# A7_POWER.net
KiCad netlist of a schematic drawn in Altium Designer
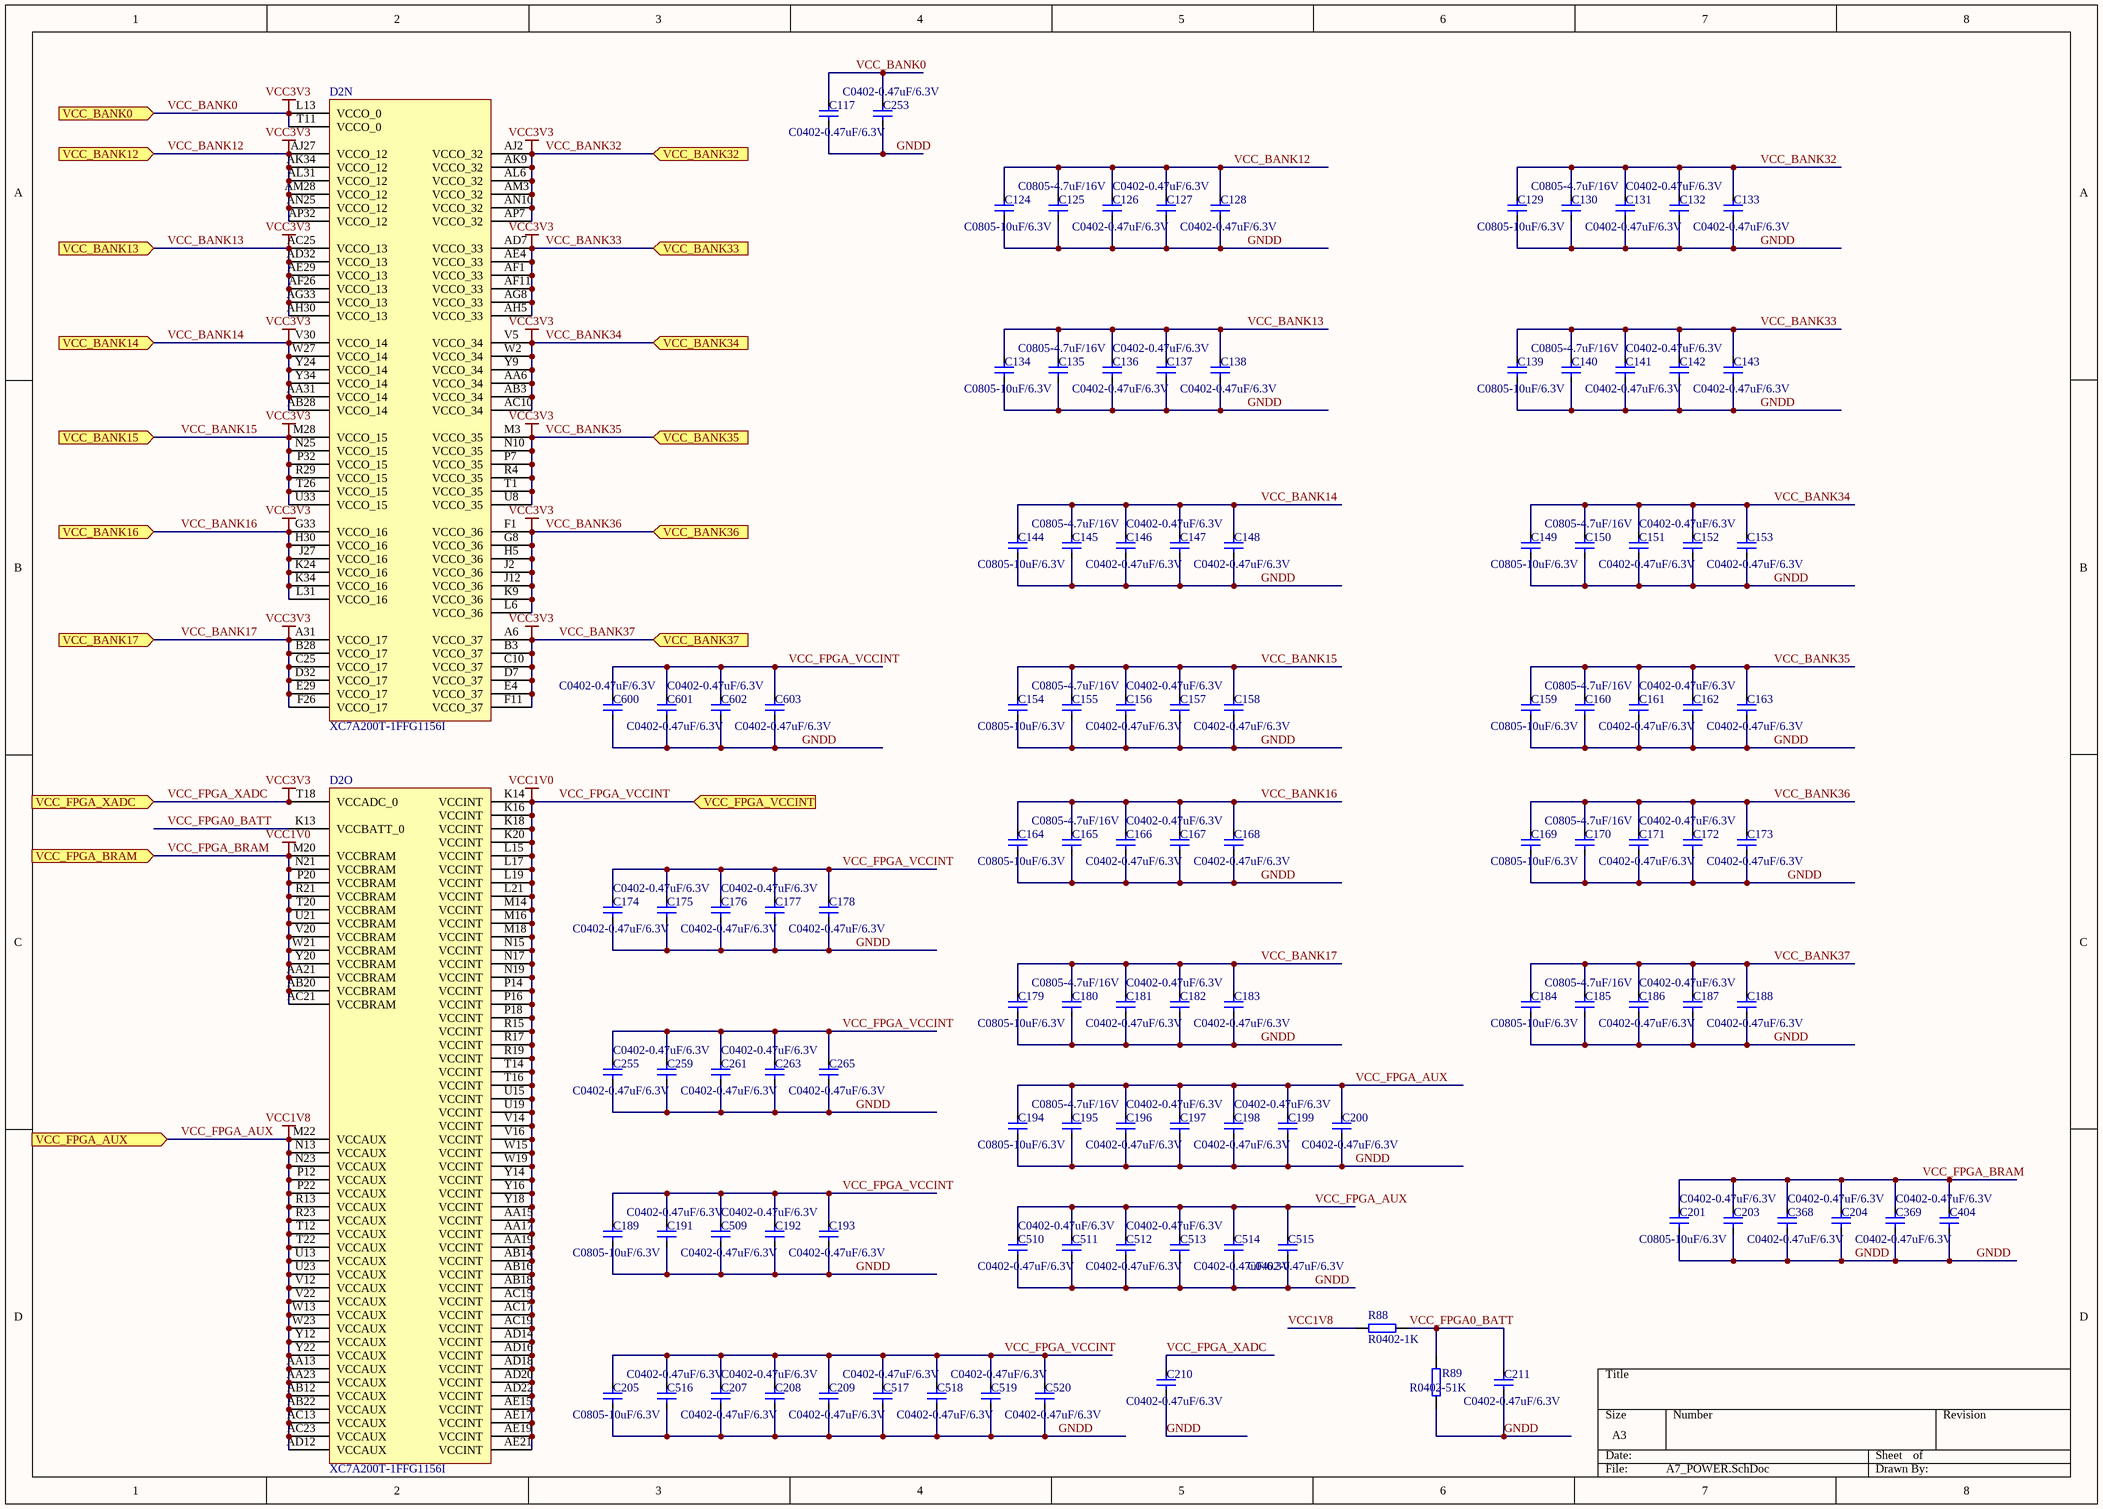
[diagram p0: A7_POWER.SchDoc]

(export (version "E")
  (design (tool "Eeschema 10.0.6"))
  (components
    (comp (ref "C117")
      (value "C0402-0.47uF/6.3V")
      (footprint "C0402")
      (description "X7R")
      (fields (field (name "SCHEMATIC_PART") "CAP") (field (name "MANUFACTURER") "SAMSUNG"))
      (libsource (lib "Database_Libs1") (part "CAP"))
    )
    (comp (ref "C124")
      (value "C0805-10uF/6.3V")
      (footprint "C0805")
      (fields (field (name "SCHEMATIC_PART") "CAP"))
      (libsource (lib "Database_Libs1") (part "CAP"))
    )
    (comp (ref "C125")
      (value "C0805-4.7uF/16V")
      (footprint "C0805")
      (description "X7R")
      (fields (field (name "SCHEMATIC_PART") "CAP") (field (name "MANUFACTURER") "SAMSUNG"))
      (libsource (lib "Database_Libs1") (part "CAP"))
    )
    (comp (ref "C126")
      (value "C0402-0.47uF/6.3V")
      (footprint "C0402")
      (description "X7R")
      (fields (field (name "SCHEMATIC_PART") "CAP") (field (name "MANUFACTURER") "SAMSUNG"))
      (libsource (lib "Database_Libs1") (part "CAP"))
    )
    (comp (ref "C127")
      (value "C0402-0.47uF/6.3V")
      (footprint "C0402")
      (description "X7R")
      (fields (field (name "SCHEMATIC_PART") "CAP") (field (name "MANUFACTURER") "SAMSUNG"))
      (libsource (lib "Database_Libs1") (part "CAP"))
    )
    (comp (ref "C128")
      (value "C0402-0.47uF/6.3V")
      (footprint "C0402")
      (description "X7R")
      (fields (field (name "SCHEMATIC_PART") "CAP") (field (name "MANUFACTURER") "SAMSUNG"))
      (libsource (lib "Database_Libs1") (part "CAP"))
    )
    (comp (ref "C129")
      (value "C0805-10uF/6.3V")
      (footprint "C0805")
      (fields (field (name "SCHEMATIC_PART") "CAP"))
      (libsource (lib "Database_Libs1") (part "CAP"))
    )
    (comp (ref "C130")
      (value "C0805-4.7uF/16V")
      (footprint "C0805")
      (description "X7R")
      (fields (field (name "SCHEMATIC_PART") "CAP") (field (name "MANUFACTURER") "SAMSUNG"))
      (libsource (lib "Database_Libs1") (part "CAP"))
    )
    (comp (ref "C131")
      (value "C0402-0.47uF/6.3V")
      (footprint "C0402")
      (description "X7R")
      (fields (field (name "SCHEMATIC_PART") "CAP") (field (name "MANUFACTURER") "SAMSUNG"))
      (libsource (lib "Database_Libs1") (part "CAP"))
    )
    (comp (ref "C132")
      (value "C0402-0.47uF/6.3V")
      (footprint "C0402")
      (description "X7R")
      (fields (field (name "SCHEMATIC_PART") "CAP") (field (name "MANUFACTURER") "SAMSUNG"))
      (libsource (lib "Database_Libs1") (part "CAP"))
    )
    (comp (ref "C133")
      (value "C0402-0.47uF/6.3V")
      (footprint "C0402")
      (description "X7R")
      (fields (field (name "SCHEMATIC_PART") "CAP") (field (name "MANUFACTURER") "SAMSUNG"))
      (libsource (lib "Database_Libs1") (part "CAP"))
    )
    (comp (ref "C134")
      (value "C0805-10uF/6.3V")
      (footprint "C0805")
      (fields (field (name "SCHEMATIC_PART") "CAP"))
      (libsource (lib "Database_Libs1") (part "CAP"))
    )
    (comp (ref "C135")
      (value "C0805-4.7uF/16V")
      (footprint "C0805")
      (description "X7R")
      (fields (field (name "SCHEMATIC_PART") "CAP") (field (name "MANUFACTURER") "SAMSUNG"))
      (libsource (lib "Database_Libs1") (part "CAP"))
    )
    (comp (ref "C136")
      (value "C0402-0.47uF/6.3V")
      (footprint "C0402")
      (description "X7R")
      (fields (field (name "SCHEMATIC_PART") "CAP") (field (name "MANUFACTURER") "SAMSUNG"))
      (libsource (lib "Database_Libs1") (part "CAP"))
    )
    (comp (ref "C137")
      (value "C0402-0.47uF/6.3V")
      (footprint "C0402")
      (description "X7R")
      (fields (field (name "SCHEMATIC_PART") "CAP") (field (name "MANUFACTURER") "SAMSUNG"))
      (libsource (lib "Database_Libs1") (part "CAP"))
    )
    (comp (ref "C138")
      (value "C0402-0.47uF/6.3V")
      (footprint "C0402")
      (description "X7R")
      (fields (field (name "SCHEMATIC_PART") "CAP") (field (name "MANUFACTURER") "SAMSUNG"))
      (libsource (lib "Database_Libs1") (part "CAP"))
    )
    (comp (ref "C139")
      (value "C0805-10uF/6.3V")
      (footprint "C0805")
      (fields (field (name "SCHEMATIC_PART") "CAP"))
      (libsource (lib "Database_Libs1") (part "CAP"))
    )
    (comp (ref "C140")
      (value "C0805-4.7uF/16V")
      (footprint "C0805")
      (description "X7R")
      (fields (field (name "SCHEMATIC_PART") "CAP") (field (name "MANUFACTURER") "SAMSUNG"))
      (libsource (lib "Database_Libs1") (part "CAP"))
    )
    (comp (ref "C141")
      (value "C0402-0.47uF/6.3V")
      (footprint "C0402")
      (description "X7R")
      (fields (field (name "SCHEMATIC_PART") "CAP") (field (name "MANUFACTURER") "SAMSUNG"))
      (libsource (lib "Database_Libs1") (part "CAP"))
    )
    (comp (ref "C142")
      (value "C0402-0.47uF/6.3V")
      (footprint "C0402")
      (description "X7R")
      (fields (field (name "SCHEMATIC_PART") "CAP") (field (name "MANUFACTURER") "SAMSUNG"))
      (libsource (lib "Database_Libs1") (part "CAP"))
    )
    (comp (ref "C143")
      (value "C0402-0.47uF/6.3V")
      (footprint "C0402")
      (description "X7R")
      (fields (field (name "SCHEMATIC_PART") "CAP") (field (name "MANUFACTURER") "SAMSUNG"))
      (libsource (lib "Database_Libs1") (part "CAP"))
    )
    (comp (ref "C144")
      (value "C0805-10uF/6.3V")
      (footprint "C0805")
      (fields (field (name "SCHEMATIC_PART") "CAP"))
      (libsource (lib "Database_Libs1") (part "CAP"))
    )
    (comp (ref "C145")
      (value "C0805-4.7uF/16V")
      (footprint "C0805")
      (description "X7R")
      (fields (field (name "SCHEMATIC_PART") "CAP") (field (name "MANUFACTURER") "SAMSUNG"))
      (libsource (lib "Database_Libs1") (part "CAP"))
    )
    (comp (ref "C146")
      (value "C0402-0.47uF/6.3V")
      (footprint "C0402")
      (description "X7R")
      (fields (field (name "SCHEMATIC_PART") "CAP") (field (name "MANUFACTURER") "SAMSUNG"))
      (libsource (lib "Database_Libs1") (part "CAP"))
    )
    (comp (ref "C147")
      (value "C0402-0.47uF/6.3V")
      (footprint "C0402")
      (description "X7R")
      (fields (field (name "SCHEMATIC_PART") "CAP") (field (name "MANUFACTURER") "SAMSUNG"))
      (libsource (lib "Database_Libs1") (part "CAP"))
    )
    (comp (ref "C148")
      (value "C0402-0.47uF/6.3V")
      (footprint "C0402")
      (description "X7R")
      (fields (field (name "SCHEMATIC_PART") "CAP") (field (name "MANUFACTURER") "SAMSUNG"))
      (libsource (lib "Database_Libs1") (part "CAP"))
    )
    (comp (ref "C149")
      (value "C0805-10uF/6.3V")
      (footprint "C0805")
      (fields (field (name "SCHEMATIC_PART") "CAP"))
      (libsource (lib "Database_Libs1") (part "CAP"))
    )
    (comp (ref "C150")
      (value "C0805-4.7uF/16V")
      (footprint "C0805")
      (description "X7R")
      (fields (field (name "SCHEMATIC_PART") "CAP") (field (name "MANUFACTURER") "SAMSUNG"))
      (libsource (lib "Database_Libs1") (part "CAP"))
    )
    (comp (ref "C151")
      (value "C0402-0.47uF/6.3V")
      (footprint "C0402")
      (description "X7R")
      (fields (field (name "SCHEMATIC_PART") "CAP") (field (name "MANUFACTURER") "SAMSUNG"))
      (libsource (lib "Database_Libs1") (part "CAP"))
    )
    (comp (ref "C152")
      (value "C0402-0.47uF/6.3V")
      (footprint "C0402")
      (description "X7R")
      (fields (field (name "SCHEMATIC_PART") "CAP") (field (name "MANUFACTURER") "SAMSUNG"))
      (libsource (lib "Database_Libs1") (part "CAP"))
    )
    (comp (ref "C153")
      (value "C0402-0.47uF/6.3V")
      (footprint "C0402")
      (description "X7R")
      (fields (field (name "SCHEMATIC_PART") "CAP") (field (name "MANUFACTURER") "SAMSUNG"))
      (libsource (lib "Database_Libs1") (part "CAP"))
    )
    (comp (ref "C154")
      (value "C0805-10uF/6.3V")
      (footprint "C0805")
      (fields (field (name "SCHEMATIC_PART") "CAP"))
      (libsource (lib "Database_Libs1") (part "CAP"))
    )
    (comp (ref "C155")
      (value "C0805-4.7uF/16V")
      (footprint "C0805")
      (description "X7R")
      (fields (field (name "SCHEMATIC_PART") "CAP") (field (name "MANUFACTURER") "SAMSUNG"))
      (libsource (lib "Database_Libs1") (part "CAP"))
    )
    (comp (ref "C156")
      (value "C0402-0.47uF/6.3V")
      (footprint "C0402")
      (description "X7R")
      (fields (field (name "SCHEMATIC_PART") "CAP") (field (name "MANUFACTURER") "SAMSUNG"))
      (libsource (lib "Database_Libs1") (part "CAP"))
    )
    (comp (ref "C157")
      (value "C0402-0.47uF/6.3V")
      (footprint "C0402")
      (description "X7R")
      (fields (field (name "SCHEMATIC_PART") "CAP") (field (name "MANUFACTURER") "SAMSUNG"))
      (libsource (lib "Database_Libs1") (part "CAP"))
    )
    (comp (ref "C158")
      (value "C0402-0.47uF/6.3V")
      (footprint "C0402")
      (description "X7R")
      (fields (field (name "SCHEMATIC_PART") "CAP") (field (name "MANUFACTURER") "SAMSUNG"))
      (libsource (lib "Database_Libs1") (part "CAP"))
    )
    (comp (ref "C159")
      (value "C0805-10uF/6.3V")
      (footprint "C0805")
      (fields (field (name "SCHEMATIC_PART") "CAP"))
      (libsource (lib "Database_Libs1") (part "CAP"))
    )
    (comp (ref "C160")
      (value "C0805-4.7uF/16V")
      (footprint "C0805")
      (description "X7R")
      (fields (field (name "SCHEMATIC_PART") "CAP") (field (name "MANUFACTURER") "SAMSUNG"))
      (libsource (lib "Database_Libs1") (part "CAP"))
    )
    (comp (ref "C161")
      (value "C0402-0.47uF/6.3V")
      (footprint "C0402")
      (description "X7R")
      (fields (field (name "SCHEMATIC_PART") "CAP") (field (name "MANUFACTURER") "SAMSUNG"))
      (libsource (lib "Database_Libs1") (part "CAP"))
    )
    (comp (ref "C162")
      (value "C0402-0.47uF/6.3V")
      (footprint "C0402")
      (description "X7R")
      (fields (field (name "SCHEMATIC_PART") "CAP") (field (name "MANUFACTURER") "SAMSUNG"))
      (libsource (lib "Database_Libs1") (part "CAP"))
    )
    (comp (ref "C163")
      (value "C0402-0.47uF/6.3V")
      (footprint "C0402")
      (description "X7R")
      (fields (field (name "SCHEMATIC_PART") "CAP") (field (name "MANUFACTURER") "SAMSUNG"))
      (libsource (lib "Database_Libs1") (part "CAP"))
    )
    (comp (ref "C164")
      (value "C0805-10uF/6.3V")
      (footprint "C0805")
      (fields (field (name "SCHEMATIC_PART") "CAP"))
      (libsource (lib "Database_Libs1") (part "CAP"))
    )
    (comp (ref "C165")
      (value "C0805-4.7uF/16V")
      (footprint "C0805")
      (description "X7R")
      (fields (field (name "SCHEMATIC_PART") "CAP") (field (name "MANUFACTURER") "SAMSUNG"))
      (libsource (lib "Database_Libs1") (part "CAP"))
    )
    (comp (ref "C166")
      (value "C0402-0.47uF/6.3V")
      (footprint "C0402")
      (description "X7R")
      (fields (field (name "SCHEMATIC_PART") "CAP") (field (name "MANUFACTURER") "SAMSUNG"))
      (libsource (lib "Database_Libs1") (part "CAP"))
    )
    (comp (ref "C167")
      (value "C0402-0.47uF/6.3V")
      (footprint "C0402")
      (description "X7R")
      (fields (field (name "SCHEMATIC_PART") "CAP") (field (name "MANUFACTURER") "SAMSUNG"))
      (libsource (lib "Database_Libs1") (part "CAP"))
    )
    (comp (ref "C168")
      (value "C0402-0.47uF/6.3V")
      (footprint "C0402")
      (description "X7R")
      (fields (field (name "SCHEMATIC_PART") "CAP") (field (name "MANUFACTURER") "SAMSUNG"))
      (libsource (lib "Database_Libs1") (part "CAP"))
    )
    (comp (ref "C169")
      (value "C0805-10uF/6.3V")
      (footprint "C0805")
      (fields (field (name "SCHEMATIC_PART") "CAP"))
      (libsource (lib "Database_Libs1") (part "CAP"))
    )
    (comp (ref "C170")
      (value "C0805-4.7uF/16V")
      (footprint "C0805")
      (description "X7R")
      (fields (field (name "SCHEMATIC_PART") "CAP") (field (name "MANUFACTURER") "SAMSUNG"))
      (libsource (lib "Database_Libs1") (part "CAP"))
    )
    (comp (ref "C171")
      (value "C0402-0.47uF/6.3V")
      (footprint "C0402")
      (description "X7R")
      (fields (field (name "SCHEMATIC_PART") "CAP") (field (name "MANUFACTURER") "SAMSUNG"))
      (libsource (lib "Database_Libs1") (part "CAP"))
    )
    (comp (ref "C172")
      (value "C0402-0.47uF/6.3V")
      (footprint "C0402")
      (description "X7R")
      (fields (field (name "SCHEMATIC_PART") "CAP") (field (name "MANUFACTURER") "SAMSUNG"))
      (libsource (lib "Database_Libs1") (part "CAP"))
    )
    (comp (ref "C173")
      (value "C0402-0.47uF/6.3V")
      (footprint "C0402")
      (description "X7R")
      (fields (field (name "SCHEMATIC_PART") "CAP") (field (name "MANUFACTURER") "SAMSUNG"))
      (libsource (lib "Database_Libs1") (part "CAP"))
    )
    (comp (ref "C174")
      (value "C0402-0.47uF/6.3V")
      (footprint "C0402")
      (description "X7R")
      (fields (field (name "SCHEMATIC_PART") "CAP") (field (name "MANUFACTURER") "SAMSUNG"))
      (libsource (lib "Database_Libs1") (part "CAP"))
    )
    (comp (ref "C175")
      (value "C0402-0.47uF/6.3V")
      (footprint "C0402")
      (description "X7R")
      (fields (field (name "SCHEMATIC_PART") "CAP") (field (name "MANUFACTURER") "SAMSUNG"))
      (libsource (lib "Database_Libs1") (part "CAP"))
    )
    (comp (ref "C176")
      (value "C0402-0.47uF/6.3V")
      (footprint "C0402")
      (description "X7R")
      (fields (field (name "SCHEMATIC_PART") "CAP") (field (name "MANUFACTURER") "SAMSUNG"))
      (libsource (lib "Database_Libs1") (part "CAP"))
    )
    (comp (ref "C177")
      (value "C0402-0.47uF/6.3V")
      (footprint "C0402")
      (description "X7R")
      (fields (field (name "SCHEMATIC_PART") "CAP") (field (name "MANUFACTURER") "SAMSUNG"))
      (libsource (lib "Database_Libs1") (part "CAP"))
    )
    (comp (ref "C178")
      (value "C0402-0.47uF/6.3V")
      (footprint "C0402")
      (description "X7R")
      (fields (field (name "SCHEMATIC_PART") "CAP") (field (name "MANUFACTURER") "SAMSUNG"))
      (libsource (lib "Database_Libs1") (part "CAP"))
    )
    (comp (ref "C179")
      (value "C0805-10uF/6.3V")
      (footprint "C0805")
      (fields (field (name "SCHEMATIC_PART") "CAP"))
      (libsource (lib "Database_Libs1") (part "CAP"))
    )
    (comp (ref "C180")
      (value "C0805-4.7uF/16V")
      (footprint "C0805")
      (description "X7R")
      (fields (field (name "SCHEMATIC_PART") "CAP") (field (name "MANUFACTURER") "SAMSUNG"))
      (libsource (lib "Database_Libs1") (part "CAP"))
    )
    (comp (ref "C181")
      (value "C0402-0.47uF/6.3V")
      (footprint "C0402")
      (description "X7R")
      (fields (field (name "SCHEMATIC_PART") "CAP") (field (name "MANUFACTURER") "SAMSUNG"))
      (libsource (lib "Database_Libs1") (part "CAP"))
    )
    (comp (ref "C182")
      (value "C0402-0.47uF/6.3V")
      (footprint "C0402")
      (description "X7R")
      (fields (field (name "SCHEMATIC_PART") "CAP") (field (name "MANUFACTURER") "SAMSUNG"))
      (libsource (lib "Database_Libs1") (part "CAP"))
    )
    (comp (ref "C183")
      (value "C0402-0.47uF/6.3V")
      (footprint "C0402")
      (description "X7R")
      (fields (field (name "SCHEMATIC_PART") "CAP") (field (name "MANUFACTURER") "SAMSUNG"))
      (libsource (lib "Database_Libs1") (part "CAP"))
    )
    (comp (ref "C184")
      (value "C0805-10uF/6.3V")
      (footprint "C0805")
      (fields (field (name "SCHEMATIC_PART") "CAP"))
      (libsource (lib "Database_Libs1") (part "CAP"))
    )
    (comp (ref "C185")
      (value "C0805-4.7uF/16V")
      (footprint "C0805")
      (description "X7R")
      (fields (field (name "SCHEMATIC_PART") "CAP") (field (name "MANUFACTURER") "SAMSUNG"))
      (libsource (lib "Database_Libs1") (part "CAP"))
    )
    (comp (ref "C186")
      (value "C0402-0.47uF/6.3V")
      (footprint "C0402")
      (description "X7R")
      (fields (field (name "SCHEMATIC_PART") "CAP") (field (name "MANUFACTURER") "SAMSUNG"))
      (libsource (lib "Database_Libs1") (part "CAP"))
    )
    (comp (ref "C187")
      (value "C0402-0.47uF/6.3V")
      (footprint "C0402")
      (description "X7R")
      (fields (field (name "SCHEMATIC_PART") "CAP") (field (name "MANUFACTURER") "SAMSUNG"))
      (libsource (lib "Database_Libs1") (part "CAP"))
    )
    (comp (ref "C188")
      (value "C0402-0.47uF/6.3V")
      (footprint "C0402")
      (description "X7R")
      (fields (field (name "SCHEMATIC_PART") "CAP") (field (name "MANUFACTURER") "SAMSUNG"))
      (libsource (lib "Database_Libs1") (part "CAP"))
    )
    (comp (ref "C189")
      (value "C0805-10uF/6.3V")
      (footprint "C0805")
      (fields (field (name "SCHEMATIC_PART") "CAP"))
      (libsource (lib "Database_Libs1") (part "CAP"))
    )
    (comp (ref "C191")
      (value "C0402-0.47uF/6.3V")
      (footprint "C0402")
      (description "X7R")
      (fields (field (name "SCHEMATIC_PART") "CAP") (field (name "MANUFACTURER") "SAMSUNG"))
      (libsource (lib "Database_Libs1") (part "CAP"))
    )
    (comp (ref "C192")
      (value "C0402-0.47uF/6.3V")
      (footprint "C0402")
      (description "X7R")
      (fields (field (name "SCHEMATIC_PART") "CAP") (field (name "MANUFACTURER") "SAMSUNG"))
      (libsource (lib "Database_Libs1") (part "CAP"))
    )
    (comp (ref "C193")
      (value "C0402-0.47uF/6.3V")
      (footprint "C0402")
      (description "X7R")
      (fields (field (name "SCHEMATIC_PART") "CAP") (field (name "MANUFACTURER") "SAMSUNG"))
      (libsource (lib "Database_Libs1") (part "CAP"))
    )
    (comp (ref "C194")
      (value "C0805-10uF/6.3V")
      (footprint "C0805")
      (fields (field (name "SCHEMATIC_PART") "CAP"))
      (libsource (lib "Database_Libs1") (part "CAP"))
    )
    (comp (ref "C195")
      (value "C0805-4.7uF/16V")
      (footprint "C0805")
      (description "X7R")
      (fields (field (name "SCHEMATIC_PART") "CAP") (field (name "MANUFACTURER") "SAMSUNG"))
      (libsource (lib "Database_Libs1") (part "CAP"))
    )
    (comp (ref "C196")
      (value "C0402-0.47uF/6.3V")
      (footprint "C0402")
      (description "X7R")
      (fields (field (name "SCHEMATIC_PART") "CAP") (field (name "MANUFACTURER") "SAMSUNG"))
      (libsource (lib "Database_Libs1") (part "CAP"))
    )
    (comp (ref "C197")
      (value "C0402-0.47uF/6.3V")
      (footprint "C0402")
      (description "X7R")
      (fields (field (name "SCHEMATIC_PART") "CAP") (field (name "MANUFACTURER") "SAMSUNG"))
      (libsource (lib "Database_Libs1") (part "CAP"))
    )
    (comp (ref "C198")
      (value "C0402-0.47uF/6.3V")
      (footprint "C0402")
      (description "X7R")
      (fields (field (name "SCHEMATIC_PART") "CAP") (field (name "MANUFACTURER") "SAMSUNG"))
      (libsource (lib "Database_Libs1") (part "CAP"))
    )
    (comp (ref "C199")
      (value "C0402-0.47uF/6.3V")
      (footprint "C0402")
      (description "X7R")
      (fields (field (name "SCHEMATIC_PART") "CAP") (field (name "MANUFACTURER") "SAMSUNG"))
      (libsource (lib "Database_Libs1") (part "CAP"))
    )
    (comp (ref "C200")
      (value "C0402-0.47uF/6.3V")
      (footprint "C0402")
      (description "X7R")
      (fields (field (name "SCHEMATIC_PART") "CAP") (field (name "MANUFACTURER") "SAMSUNG"))
      (libsource (lib "Database_Libs1") (part "CAP"))
    )
    (comp (ref "C201")
      (value "C0805-10uF/6.3V")
      (footprint "C0805")
      (fields (field (name "SCHEMATIC_PART") "CAP"))
      (libsource (lib "Database_Libs1") (part "CAP"))
    )
    (comp (ref "C203")
      (value "C0402-0.47uF/6.3V")
      (footprint "C0402")
      (description "X7R")
      (fields (field (name "SCHEMATIC_PART") "CAP") (field (name "MANUFACTURER") "SAMSUNG"))
      (libsource (lib "Database_Libs1") (part "CAP"))
    )
    (comp (ref "C204")
      (value "C0402-0.47uF/6.3V")
      (footprint "C0402")
      (description "X7R")
      (fields (field (name "SCHEMATIC_PART") "CAP") (field (name "MANUFACTURER") "SAMSUNG"))
      (libsource (lib "Database_Libs1") (part "CAP"))
    )
    (comp (ref "C205")
      (value "C0805-10uF/6.3V")
      (footprint "C0805")
      (fields (field (name "SCHEMATIC_PART") "CAP"))
      (libsource (lib "Database_Libs1") (part "CAP"))
    )
    (comp (ref "C207")
      (value "C0402-0.47uF/6.3V")
      (footprint "C0402")
      (description "X7R")
      (fields (field (name "SCHEMATIC_PART") "CAP") (field (name "MANUFACTURER") "SAMSUNG"))
      (libsource (lib "Database_Libs1") (part "CAP"))
    )
    (comp (ref "C208")
      (value "C0402-0.47uF/6.3V")
      (footprint "C0402")
      (description "X7R")
      (fields (field (name "SCHEMATIC_PART") "CAP") (field (name "MANUFACTURER") "SAMSUNG"))
      (libsource (lib "Database_Libs1") (part "CAP"))
    )
    (comp (ref "C209")
      (value "C0402-0.47uF/6.3V")
      (footprint "C0402")
      (description "X7R")
      (fields (field (name "SCHEMATIC_PART") "CAP") (field (name "MANUFACTURER") "SAMSUNG"))
      (libsource (lib "Database_Libs1") (part "CAP"))
    )
    (comp (ref "C210")
      (value "C0402-0.47uF/6.3V")
      (footprint "C0402")
      (description "X7R")
      (fields (field (name "SCHEMATIC_PART") "CAP") (field (name "MANUFACTURER") "SAMSUNG"))
      (libsource (lib "Database_Libs1") (part "CAP"))
    )
    (comp (ref "C211")
      (value "C0402-0.47uF/6.3V")
      (footprint "C0402")
      (description "X7R")
      (fields (field (name "SCHEMATIC_PART") "CAP") (field (name "MANUFACTURER") "SAMSUNG"))
      (libsource (lib "Database_Libs1") (part "CAP"))
    )
    (comp (ref "C253")
      (value "C0402-0.47uF/6.3V")
      (footprint "C0402")
      (description "X7R")
      (fields (field (name "SCHEMATIC_PART") "CAP") (field (name "MANUFACTURER") "SAMSUNG"))
      (libsource (lib "Database_Libs1") (part "CAP"))
    )
    (comp (ref "C255")
      (value "C0402-0.47uF/6.3V")
      (footprint "C0402")
      (description "X7R")
      (fields (field (name "SCHEMATIC_PART") "CAP") (field (name "MANUFACTURER") "SAMSUNG"))
      (libsource (lib "Database_Libs1") (part "CAP"))
    )
    (comp (ref "C259")
      (value "C0402-0.47uF/6.3V")
      (footprint "C0402")
      (description "X7R")
      (fields (field (name "SCHEMATIC_PART") "CAP") (field (name "MANUFACTURER") "SAMSUNG"))
      (libsource (lib "Database_Libs1") (part "CAP"))
    )
    (comp (ref "C261")
      (value "C0402-0.47uF/6.3V")
      (footprint "C0402")
      (description "X7R")
      (fields (field (name "SCHEMATIC_PART") "CAP") (field (name "MANUFACTURER") "SAMSUNG"))
      (libsource (lib "Database_Libs1") (part "CAP"))
    )
    (comp (ref "C263")
      (value "C0402-0.47uF/6.3V")
      (footprint "C0402")
      (description "X7R")
      (fields (field (name "SCHEMATIC_PART") "CAP") (field (name "MANUFACTURER") "SAMSUNG"))
      (libsource (lib "Database_Libs1") (part "CAP"))
    )
    (comp (ref "C265")
      (value "C0402-0.47uF/6.3V")
      (footprint "C0402")
      (description "X7R")
      (fields (field (name "SCHEMATIC_PART") "CAP") (field (name "MANUFACTURER") "SAMSUNG"))
      (libsource (lib "Database_Libs1") (part "CAP"))
    )
    (comp (ref "C368")
      (value "C0402-0.47uF/6.3V")
      (footprint "C0402")
      (description "X7R")
      (fields (field (name "SCHEMATIC_PART") "CAP") (field (name "MANUFACTURER") "SAMSUNG"))
      (libsource (lib "Database_Libs1") (part "CAP"))
    )
    (comp (ref "C369")
      (value "C0402-0.47uF/6.3V")
      (footprint "C0402")
      (description "X7R")
      (fields (field (name "SCHEMATIC_PART") "CAP") (field (name "MANUFACTURER") "SAMSUNG"))
      (libsource (lib "Database_Libs1") (part "CAP"))
    )
    (comp (ref "C404")
      (value "C0402-0.47uF/6.3V")
      (footprint "C0402")
      (description "X7R")
      (fields (field (name "SCHEMATIC_PART") "CAP") (field (name "MANUFACTURER") "SAMSUNG"))
      (libsource (lib "Database_Libs1") (part "CAP"))
    )
    (comp (ref "C509")
      (value "C0402-0.47uF/6.3V")
      (footprint "C0402")
      (description "X7R")
      (fields (field (name "SCHEMATIC_PART") "CAP") (field (name "MANUFACTURER") "SAMSUNG"))
      (libsource (lib "Database_Libs1") (part "CAP"))
    )
    (comp (ref "C510")
      (value "C0402-0.47uF/6.3V")
      (footprint "C0402")
      (description "X7R")
      (fields (field (name "SCHEMATIC_PART") "CAP") (field (name "MANUFACTURER") "SAMSUNG"))
      (libsource (lib "Database_Libs1") (part "CAP"))
    )
    (comp (ref "C511")
      (value "C0402-0.47uF/6.3V")
      (footprint "C0402")
      (description "X7R")
      (fields (field (name "SCHEMATIC_PART") "CAP") (field (name "MANUFACTURER") "SAMSUNG"))
      (libsource (lib "Database_Libs1") (part "CAP"))
    )
    (comp (ref "C512")
      (value "C0402-0.47uF/6.3V")
      (footprint "C0402")
      (description "X7R")
      (fields (field (name "SCHEMATIC_PART") "CAP") (field (name "MANUFACTURER") "SAMSUNG"))
      (libsource (lib "Database_Libs1") (part "CAP"))
    )
    (comp (ref "C513")
      (value "C0402-0.47uF/6.3V")
      (footprint "C0402")
      (description "X7R")
      (fields (field (name "SCHEMATIC_PART") "CAP") (field (name "MANUFACTURER") "SAMSUNG"))
      (libsource (lib "Database_Libs1") (part "CAP"))
    )
    (comp (ref "C514")
      (value "C0402-0.47uF/6.3V")
      (footprint "C0402")
      (description "X7R")
      (fields (field (name "SCHEMATIC_PART") "CAP") (field (name "MANUFACTURER") "SAMSUNG"))
      (libsource (lib "Database_Libs1") (part "CAP"))
    )
    (comp (ref "C515")
      (value "C0402-0.47uF/6.3V")
      (footprint "C0402")
      (description "X7R")
      (fields (field (name "SCHEMATIC_PART") "CAP") (field (name "MANUFACTURER") "SAMSUNG"))
      (libsource (lib "Database_Libs1") (part "CAP"))
    )
    (comp (ref "C516")
      (value "C0402-0.47uF/6.3V")
      (footprint "C0402")
      (description "X7R")
      (fields (field (name "SCHEMATIC_PART") "CAP") (field (name "MANUFACTURER") "SAMSUNG"))
      (libsource (lib "Database_Libs1") (part "CAP"))
    )
    (comp (ref "C517")
      (value "C0402-0.47uF/6.3V")
      (footprint "C0402")
      (description "X7R")
      (fields (field (name "SCHEMATIC_PART") "CAP") (field (name "MANUFACTURER") "SAMSUNG"))
      (libsource (lib "Database_Libs1") (part "CAP"))
    )
    (comp (ref "C518")
      (value "C0402-0.47uF/6.3V")
      (footprint "C0402")
      (description "X7R")
      (fields (field (name "SCHEMATIC_PART") "CAP") (field (name "MANUFACTURER") "SAMSUNG"))
      (libsource (lib "Database_Libs1") (part "CAP"))
    )
    (comp (ref "C519")
      (value "C0402-0.47uF/6.3V")
      (footprint "C0402")
      (description "X7R")
      (fields (field (name "SCHEMATIC_PART") "CAP") (field (name "MANUFACTURER") "SAMSUNG"))
      (libsource (lib "Database_Libs1") (part "CAP"))
    )
    (comp (ref "C520")
      (value "C0402-0.47uF/6.3V")
      (footprint "C0402")
      (description "X7R")
      (fields (field (name "SCHEMATIC_PART") "CAP") (field (name "MANUFACTURER") "SAMSUNG"))
      (libsource (lib "Database_Libs1") (part "CAP"))
    )
    (comp (ref "C600")
      (value "C0402-0.47uF/6.3V")
      (footprint "C0402")
      (description "X7R")
      (fields (field (name "SCHEMATIC_PART") "CAP") (field (name "MANUFACTURER") "SAMSUNG"))
      (libsource (lib "Database_Libs1") (part "CAP"))
    )
    (comp (ref "C601")
      (value "C0402-0.47uF/6.3V")
      (footprint "C0402")
      (description "X7R")
      (fields (field (name "SCHEMATIC_PART") "CAP") (field (name "MANUFACTURER") "SAMSUNG"))
      (libsource (lib "Database_Libs1") (part "CAP"))
    )
    (comp (ref "C602")
      (value "C0402-0.47uF/6.3V")
      (footprint "C0402")
      (description "X7R")
      (fields (field (name "SCHEMATIC_PART") "CAP") (field (name "MANUFACTURER") "SAMSUNG"))
      (libsource (lib "Database_Libs1") (part "CAP"))
    )
    (comp (ref "C603")
      (value "C0402-0.47uF/6.3V")
      (footprint "C0402")
      (description "X7R")
      (fields (field (name "SCHEMATIC_PART") "CAP") (field (name "MANUFACTURER") "SAMSUNG"))
      (libsource (lib "Database_Libs1") (part "CAP"))
    )
    (comp (ref "D2")
      (value "XC7A200T-1FFG1156I")
      (footprint "FFG1156")
      (description "Artix-7 FPGA, 500 User I/Os, 16 GTP, 1156-Ball BGA, Speed Grade 1, Industrial Grade, Pb-Free")
      (fields (field (name "GENERIC PART NUMBER") "XC7A200T") (field (name "MANUFACTURER") "Xilinx"))
      (libsource (lib "Xilinx Artix-7") (part "XC7A200T-1FFG1156I"))
    )
    (comp (ref "R88")
      (value "R0402-1K")
      (footprint "R0402")
      (fields (field (name "SCHEMATIC_PART") "RES") (field (name "MANUFACTURER") "SAMSUNG"))
      (libsource (lib "Database_Libs1") (part "RES"))
    )
    (comp (ref "R89")
      (value "R0402-51K")
      (footprint "R0402")
      (fields (field (name "SCHEMATIC_PART") "RES") (field (name "MANUFACTURER") "SAMSUNG"))
      (libsource (lib "Database_Libs1") (part "RES"))
    )
  )
  (nets
    (net (code "1") (name "/GNDD") (class "Default")
      (node (ref "C117") (pin "2") (pinfunction "2_2") (pintype "passive"))
      (node (ref "C124") (pin "2") (pinfunction "2_2") (pintype "passive"))
      (node (ref "C125") (pin "2") (pinfunction "2_2") (pintype "passive"))
      (node (ref "C126") (pin "2") (pinfunction "2_2") (pintype "passive"))
      (node (ref "C127") (pin "2") (pinfunction "2_2") (pintype "passive"))
      (node (ref "C128") (pin "2") (pinfunction "2_2") (pintype "passive"))
      (node (ref "C129") (pin "2") (pinfunction "2_2") (pintype "passive"))
      (node (ref "C130") (pin "2") (pinfunction "2_2") (pintype "passive"))
      (node (ref "C131") (pin "2") (pinfunction "2_2") (pintype "passive"))
      (node (ref "C132") (pin "2") (pinfunction "2_2") (pintype "passive"))
      (node (ref "C133") (pin "2") (pinfunction "2_2") (pintype "passive"))
      (node (ref "C134") (pin "2") (pinfunction "2_2") (pintype "passive"))
      (node (ref "C135") (pin "2") (pinfunction "2_2") (pintype "passive"))
      (node (ref "C136") (pin "2") (pinfunction "2_2") (pintype "passive"))
      (node (ref "C137") (pin "2") (pinfunction "2_2") (pintype "passive"))
      (node (ref "C138") (pin "2") (pinfunction "2_2") (pintype "passive"))
      (node (ref "C139") (pin "2") (pinfunction "2_2") (pintype "passive"))
      (node (ref "C140") (pin "2") (pinfunction "2_2") (pintype "passive"))
      (node (ref "C141") (pin "2") (pinfunction "2_2") (pintype "passive"))
      (node (ref "C142") (pin "2") (pinfunction "2_2") (pintype "passive"))
      (node (ref "C143") (pin "2") (pinfunction "2_2") (pintype "passive"))
      (node (ref "C144") (pin "2") (pinfunction "2_2") (pintype "passive"))
      (node (ref "C145") (pin "2") (pinfunction "2_2") (pintype "passive"))
      (node (ref "C146") (pin "2") (pinfunction "2_2") (pintype "passive"))
      (node (ref "C147") (pin "2") (pinfunction "2_2") (pintype "passive"))
      (node (ref "C148") (pin "2") (pinfunction "2_2") (pintype "passive"))
      (node (ref "C149") (pin "2") (pinfunction "2_2") (pintype "passive"))
      (node (ref "C150") (pin "2") (pinfunction "2_2") (pintype "passive"))
      (node (ref "C151") (pin "2") (pinfunction "2_2") (pintype "passive"))
      (node (ref "C152") (pin "2") (pinfunction "2_2") (pintype "passive"))
      (node (ref "C153") (pin "2") (pinfunction "2_2") (pintype "passive"))
      (node (ref "C154") (pin "2") (pinfunction "2_2") (pintype "passive"))
      (node (ref "C155") (pin "2") (pinfunction "2_2") (pintype "passive"))
      (node (ref "C156") (pin "2") (pinfunction "2_2") (pintype "passive"))
      (node (ref "C157") (pin "2") (pinfunction "2_2") (pintype "passive"))
      (node (ref "C158") (pin "2") (pinfunction "2_2") (pintype "passive"))
      (node (ref "C159") (pin "2") (pinfunction "2_2") (pintype "passive"))
      (node (ref "C160") (pin "2") (pinfunction "2_2") (pintype "passive"))
      (node (ref "C161") (pin "2") (pinfunction "2_2") (pintype "passive"))
      (node (ref "C162") (pin "2") (pinfunction "2_2") (pintype "passive"))
      (node (ref "C163") (pin "2") (pinfunction "2_2") (pintype "passive"))
      (node (ref "C164") (pin "2") (pinfunction "2_2") (pintype "passive"))
      (node (ref "C165") (pin "2") (pinfunction "2_2") (pintype "passive"))
      (node (ref "C166") (pin "2") (pinfunction "2_2") (pintype "passive"))
      (node (ref "C167") (pin "2") (pinfunction "2_2") (pintype "passive"))
      (node (ref "C168") (pin "2") (pinfunction "2_2") (pintype "passive"))
      (node (ref "C169") (pin "2") (pinfunction "2_2") (pintype "passive"))
      (node (ref "C170") (pin "2") (pinfunction "2_2") (pintype "passive"))
      (node (ref "C171") (pin "2") (pinfunction "2_2") (pintype "passive"))
      (node (ref "C172") (pin "2") (pinfunction "2_2") (pintype "passive"))
      (node (ref "C173") (pin "2") (pinfunction "2_2") (pintype "passive"))
      (node (ref "C174") (pin "2") (pinfunction "2_2") (pintype "passive"))
      (node (ref "C175") (pin "2") (pinfunction "2_2") (pintype "passive"))
      (node (ref "C176") (pin "2") (pinfunction "2_2") (pintype "passive"))
      (node (ref "C177") (pin "2") (pinfunction "2_2") (pintype "passive"))
      (node (ref "C178") (pin "2") (pinfunction "2_2") (pintype "passive"))
      (node (ref "C179") (pin "2") (pinfunction "2_2") (pintype "passive"))
      (node (ref "C180") (pin "2") (pinfunction "2_2") (pintype "passive"))
      (node (ref "C181") (pin "2") (pinfunction "2_2") (pintype "passive"))
      (node (ref "C182") (pin "2") (pinfunction "2_2") (pintype "passive"))
      (node (ref "C183") (pin "2") (pinfunction "2_2") (pintype "passive"))
      (node (ref "C184") (pin "2") (pinfunction "2_2") (pintype "passive"))
      (node (ref "C185") (pin "2") (pinfunction "2_2") (pintype "passive"))
      (node (ref "C186") (pin "2") (pinfunction "2_2") (pintype "passive"))
      (node (ref "C187") (pin "2") (pinfunction "2_2") (pintype "passive"))
      (node (ref "C188") (pin "2") (pinfunction "2_2") (pintype "passive"))
      (node (ref "C189") (pin "2") (pinfunction "2_2") (pintype "passive"))
      (node (ref "C191") (pin "2") (pinfunction "2_2") (pintype "passive"))
      (node (ref "C192") (pin "2") (pinfunction "2_2") (pintype "passive"))
      (node (ref "C193") (pin "2") (pinfunction "2_2") (pintype "passive"))
      (node (ref "C194") (pin "2") (pinfunction "2_2") (pintype "passive"))
      (node (ref "C195") (pin "2") (pinfunction "2_2") (pintype "passive"))
      (node (ref "C196") (pin "2") (pinfunction "2_2") (pintype "passive"))
      (node (ref "C197") (pin "2") (pinfunction "2_2") (pintype "passive"))
      (node (ref "C198") (pin "2") (pinfunction "2_2") (pintype "passive"))
      (node (ref "C199") (pin "2") (pinfunction "2_2") (pintype "passive"))
      (node (ref "C200") (pin "2") (pinfunction "2_2") (pintype "passive"))
      (node (ref "C201") (pin "2") (pinfunction "2_2") (pintype "passive"))
      (node (ref "C203") (pin "2") (pinfunction "2_2") (pintype "passive"))
      (node (ref "C204") (pin "2") (pinfunction "2_2") (pintype "passive"))
      (node (ref "C205") (pin "2") (pinfunction "2_2") (pintype "passive"))
      (node (ref "C207") (pin "2") (pinfunction "2_2") (pintype "passive"))
      (node (ref "C208") (pin "2") (pinfunction "2_2") (pintype "passive"))
      (node (ref "C209") (pin "2") (pinfunction "2_2") (pintype "passive"))
      (node (ref "C210") (pin "2") (pinfunction "2_2") (pintype "passive"))
      (node (ref "C211") (pin "2") (pinfunction "2_2") (pintype "passive"))
      (node (ref "C253") (pin "2") (pinfunction "2_2") (pintype "passive"))
      (node (ref "C255") (pin "2") (pinfunction "2_2") (pintype "passive"))
      (node (ref "C259") (pin "2") (pinfunction "2_2") (pintype "passive"))
      (node (ref "C261") (pin "2") (pinfunction "2_2") (pintype "passive"))
      (node (ref "C263") (pin "2") (pinfunction "2_2") (pintype "passive"))
      (node (ref "C265") (pin "2") (pinfunction "2_2") (pintype "passive"))
      (node (ref "C368") (pin "2") (pinfunction "2_2") (pintype "passive"))
      (node (ref "C369") (pin "2") (pinfunction "2_2") (pintype "passive"))
      (node (ref "C404") (pin "2") (pinfunction "2_2") (pintype "passive"))
      (node (ref "C509") (pin "2") (pinfunction "2_2") (pintype "passive"))
      (node (ref "C510") (pin "2") (pinfunction "2_2") (pintype "passive"))
      (node (ref "C511") (pin "2") (pinfunction "2_2") (pintype "passive"))
      (node (ref "C512") (pin "2") (pinfunction "2_2") (pintype "passive"))
      (node (ref "C513") (pin "2") (pinfunction "2_2") (pintype "passive"))
      (node (ref "C514") (pin "2") (pinfunction "2_2") (pintype "passive"))
      (node (ref "C515") (pin "2") (pinfunction "2_2") (pintype "passive"))
      (node (ref "C516") (pin "2") (pinfunction "2_2") (pintype "passive"))
      (node (ref "C517") (pin "2") (pinfunction "2_2") (pintype "passive"))
      (node (ref "C518") (pin "2") (pinfunction "2_2") (pintype "passive"))
      (node (ref "C519") (pin "2") (pinfunction "2_2") (pintype "passive"))
      (node (ref "C520") (pin "2") (pinfunction "2_2") (pintype "passive"))
      (node (ref "C600") (pin "2") (pinfunction "2_2") (pintype "passive"))
      (node (ref "C601") (pin "2") (pinfunction "2_2") (pintype "passive"))
      (node (ref "C602") (pin "2") (pinfunction "2_2") (pintype "passive"))
      (node (ref "C603") (pin "2") (pinfunction "2_2") (pintype "passive"))
      (node (ref "R89") (pin "1") (pintype "passive"))
    )
    (net (code "2") (name "/VCC_FPGA0_BATT") (class "Default")
      (node (ref "C211") (pin "1") (pinfunction "1_1") (pintype "passive"))
      (node (ref "D2") (pin "K13") (pinfunction "VCCBATT_0_K13") (pintype "power_in"))
      (node (ref "R88") (pin "1") (pintype "passive"))
      (node (ref "R89") (pin "2") (pintype "passive"))
    )
    (net (code "3") (name "VCC1V0") (class "Default")
      (node (ref "C174") (pin "1") (pinfunction "1_1") (pintype "passive"))
      (node (ref "C175") (pin "1") (pinfunction "1_1") (pintype "passive"))
      (node (ref "C176") (pin "1") (pinfunction "1_1") (pintype "passive"))
      (node (ref "C177") (pin "1") (pinfunction "1_1") (pintype "passive"))
      (node (ref "C178") (pin "1") (pinfunction "1_1") (pintype "passive"))
      (node (ref "C189") (pin "1") (pinfunction "1_1") (pintype "passive"))
      (node (ref "C191") (pin "1") (pinfunction "1_1") (pintype "passive"))
      (node (ref "C192") (pin "1") (pinfunction "1_1") (pintype "passive"))
      (node (ref "C193") (pin "1") (pinfunction "1_1") (pintype "passive"))
      (node (ref "C201") (pin "1") (pinfunction "1_1") (pintype "passive"))
      (node (ref "C203") (pin "1") (pinfunction "1_1") (pintype "passive"))
      (node (ref "C204") (pin "1") (pinfunction "1_1") (pintype "passive"))
      (node (ref "C205") (pin "1") (pinfunction "1_1") (pintype "passive"))
      (node (ref "C207") (pin "1") (pinfunction "1_1") (pintype "passive"))
      (node (ref "C208") (pin "1") (pinfunction "1_1") (pintype "passive"))
      (node (ref "C209") (pin "1") (pinfunction "1_1") (pintype "passive"))
      (node (ref "C255") (pin "1") (pinfunction "1_1") (pintype "passive"))
      (node (ref "C259") (pin "1") (pinfunction "1_1") (pintype "passive"))
      (node (ref "C261") (pin "1") (pinfunction "1_1") (pintype "passive"))
      (node (ref "C263") (pin "1") (pinfunction "1_1") (pintype "passive"))
      (node (ref "C265") (pin "1") (pinfunction "1_1") (pintype "passive"))
      (node (ref "C368") (pin "1") (pinfunction "1_1") (pintype "passive"))
      (node (ref "C369") (pin "1") (pinfunction "1_1") (pintype "passive"))
      (node (ref "C404") (pin "1") (pinfunction "1_1") (pintype "passive"))
      (node (ref "C509") (pin "1") (pinfunction "1_1") (pintype "passive"))
      (node (ref "C516") (pin "1") (pinfunction "1_1") (pintype "passive"))
      (node (ref "C517") (pin "1") (pinfunction "1_1") (pintype "passive"))
      (node (ref "C518") (pin "1") (pinfunction "1_1") (pintype "passive"))
      (node (ref "C519") (pin "1") (pinfunction "1_1") (pintype "passive"))
      (node (ref "C520") (pin "1") (pinfunction "1_1") (pintype "passive"))
      (node (ref "C600") (pin "1") (pinfunction "1_1") (pintype "passive"))
      (node (ref "C601") (pin "1") (pinfunction "1_1") (pintype "passive"))
      (node (ref "C602") (pin "1") (pinfunction "1_1") (pintype "passive"))
      (node (ref "C603") (pin "1") (pinfunction "1_1") (pintype "passive"))
      (node (ref "D2") (pin "AA15") (pinfunction "VCCINT_AA15") (pintype "power_in"))
      (node (ref "D2") (pin "AA17") (pinfunction "VCCINT_AA17") (pintype "power_in"))
      (node (ref "D2") (pin "AA19") (pinfunction "VCCINT_AA19") (pintype "power_in"))
      (node (ref "D2") (pin "AA21") (pinfunction "VCCBRAM_AA21") (pintype "power_in"))
      (node (ref "D2") (pin "AB14") (pinfunction "VCCINT_AB14") (pintype "power_in"))
      (node (ref "D2") (pin "AB16") (pinfunction "VCCINT_AB16") (pintype "power_in"))
      (node (ref "D2") (pin "AB18") (pinfunction "VCCINT_AB18") (pintype "power_in"))
      (node (ref "D2") (pin "AB20") (pinfunction "VCCBRAM_AB20") (pintype "power_in"))
      (node (ref "D2") (pin "AC15") (pinfunction "VCCINT_AC15") (pintype "power_in"))
      (node (ref "D2") (pin "AC17") (pinfunction "VCCINT_AC17") (pintype "power_in"))
      (node (ref "D2") (pin "AC19") (pinfunction "VCCINT_AC19") (pintype "power_in"))
      (node (ref "D2") (pin "AC21") (pinfunction "VCCBRAM_AC21") (pintype "power_in"))
      (node (ref "D2") (pin "AD14") (pinfunction "VCCINT_AD14") (pintype "power_in"))
      (node (ref "D2") (pin "AD16") (pinfunction "VCCINT_AD16") (pintype "power_in"))
      (node (ref "D2") (pin "AD18") (pinfunction "VCCINT_AD18") (pintype "power_in"))
      (node (ref "D2") (pin "AD20") (pinfunction "VCCINT_AD20") (pintype "power_in"))
      (node (ref "D2") (pin "AD22") (pinfunction "VCCINT_AD22") (pintype "power_in"))
      (node (ref "D2") (pin "AE15") (pinfunction "VCCINT_AE15") (pintype "power_in"))
      (node (ref "D2") (pin "AE17") (pinfunction "VCCINT_AE17") (pintype "power_in"))
      (node (ref "D2") (pin "AE19") (pinfunction "VCCINT_AE19") (pintype "power_in"))
      (node (ref "D2") (pin "AE21") (pinfunction "VCCINT_AE21") (pintype "power_in"))
      (node (ref "D2") (pin "K14") (pinfunction "VCCINT_K14") (pintype "power_in"))
      (node (ref "D2") (pin "K16") (pinfunction "VCCINT_K16") (pintype "power_in"))
      (node (ref "D2") (pin "K18") (pinfunction "VCCINT_K18") (pintype "power_in"))
      (node (ref "D2") (pin "K20") (pinfunction "VCCINT_K20") (pintype "power_in"))
      (node (ref "D2") (pin "L15") (pinfunction "VCCINT_L15") (pintype "power_in"))
      (node (ref "D2") (pin "L17") (pinfunction "VCCINT_L17") (pintype "power_in"))
      (node (ref "D2") (pin "L19") (pinfunction "VCCINT_L19") (pintype "power_in"))
      (node (ref "D2") (pin "L21") (pinfunction "VCCINT_L21") (pintype "power_in"))
      (node (ref "D2") (pin "M14") (pinfunction "VCCINT_M14") (pintype "power_in"))
      (node (ref "D2") (pin "M16") (pinfunction "VCCINT_M16") (pintype "power_in"))
      (node (ref "D2") (pin "M18") (pinfunction "VCCINT_M18") (pintype "power_in"))
      (node (ref "D2") (pin "M20") (pinfunction "VCCBRAM_M20") (pintype "power_in"))
      (node (ref "D2") (pin "N15") (pinfunction "VCCINT_N15") (pintype "power_in"))
      (node (ref "D2") (pin "N17") (pinfunction "VCCINT_N17") (pintype "power_in"))
      (node (ref "D2") (pin "N19") (pinfunction "VCCINT_N19") (pintype "power_in"))
      (node (ref "D2") (pin "N21") (pinfunction "VCCBRAM_N21") (pintype "power_in"))
      (node (ref "D2") (pin "P14") (pinfunction "VCCINT_P14") (pintype "power_in"))
      (node (ref "D2") (pin "P16") (pinfunction "VCCINT_P16") (pintype "power_in"))
      (node (ref "D2") (pin "P18") (pinfunction "VCCINT_P18") (pintype "power_in"))
      (node (ref "D2") (pin "P20") (pinfunction "VCCBRAM_P20") (pintype "power_in"))
      (node (ref "D2") (pin "R15") (pinfunction "VCCINT_R15") (pintype "power_in"))
      (node (ref "D2") (pin "R17") (pinfunction "VCCINT_R17") (pintype "power_in"))
      (node (ref "D2") (pin "R19") (pinfunction "VCCINT_R19") (pintype "power_in"))
      (node (ref "D2") (pin "R21") (pinfunction "VCCBRAM_R21") (pintype "power_in"))
      (node (ref "D2") (pin "T14") (pinfunction "VCCINT_T14") (pintype "power_in"))
      (node (ref "D2") (pin "T16") (pinfunction "VCCINT_T16") (pintype "power_in"))
      (node (ref "D2") (pin "T20") (pinfunction "VCCBRAM_T20") (pintype "power_in"))
      (node (ref "D2") (pin "U15") (pinfunction "VCCINT_U15") (pintype "power_in"))
      (node (ref "D2") (pin "U19") (pinfunction "VCCINT_U19") (pintype "power_in"))
      (node (ref "D2") (pin "U21") (pinfunction "VCCBRAM_U21") (pintype "power_in"))
      (node (ref "D2") (pin "V14") (pinfunction "VCCINT_V14") (pintype "power_in"))
      (node (ref "D2") (pin "V16") (pinfunction "VCCINT_V16") (pintype "power_in"))
      (node (ref "D2") (pin "V20") (pinfunction "VCCBRAM_V20") (pintype "power_in"))
      (node (ref "D2") (pin "W15") (pinfunction "VCCINT_W15") (pintype "power_in"))
      (node (ref "D2") (pin "W19") (pinfunction "VCCINT_W19") (pintype "power_in"))
      (node (ref "D2") (pin "W21") (pinfunction "VCCBRAM_W21") (pintype "power_in"))
      (node (ref "D2") (pin "Y14") (pinfunction "VCCINT_Y14") (pintype "power_in"))
      (node (ref "D2") (pin "Y16") (pinfunction "VCCINT_Y16") (pintype "power_in"))
      (node (ref "D2") (pin "Y18") (pinfunction "VCCINT_Y18") (pintype "power_in"))
      (node (ref "D2") (pin "Y20") (pinfunction "VCCBRAM_Y20") (pintype "power_in"))
    )
    (net (code "4") (name "VCC1V8") (class "Default")
      (node (ref "C194") (pin "1") (pinfunction "1_1") (pintype "passive"))
      (node (ref "C195") (pin "1") (pinfunction "1_1") (pintype "passive"))
      (node (ref "C196") (pin "1") (pinfunction "1_1") (pintype "passive"))
      (node (ref "C197") (pin "1") (pinfunction "1_1") (pintype "passive"))
      (node (ref "C198") (pin "1") (pinfunction "1_1") (pintype "passive"))
      (node (ref "C199") (pin "1") (pinfunction "1_1") (pintype "passive"))
      (node (ref "C200") (pin "1") (pinfunction "1_1") (pintype "passive"))
      (node (ref "C510") (pin "1") (pinfunction "1_1") (pintype "passive"))
      (node (ref "C511") (pin "1") (pinfunction "1_1") (pintype "passive"))
      (node (ref "C512") (pin "1") (pinfunction "1_1") (pintype "passive"))
      (node (ref "C513") (pin "1") (pinfunction "1_1") (pintype "passive"))
      (node (ref "C514") (pin "1") (pinfunction "1_1") (pintype "passive"))
      (node (ref "C515") (pin "1") (pinfunction "1_1") (pintype "passive"))
      (node (ref "D2") (pin "AA13") (pinfunction "VCCAUX_AA13") (pintype "power_in"))
      (node (ref "D2") (pin "AA23") (pinfunction "VCCAUX_AA23") (pintype "power_in"))
      (node (ref "D2") (pin "AB12") (pinfunction "VCCAUX_AB12") (pintype "power_in"))
      (node (ref "D2") (pin "AB22") (pinfunction "VCCAUX_AB22") (pintype "power_in"))
      (node (ref "D2") (pin "AC13") (pinfunction "VCCAUX_AC13") (pintype "power_in"))
      (node (ref "D2") (pin "AC23") (pinfunction "VCCAUX_AC23") (pintype "power_in"))
      (node (ref "D2") (pin "AD12") (pinfunction "VCCAUX_AD12") (pintype "power_in"))
      (node (ref "D2") (pin "M22") (pinfunction "VCCAUX_M22") (pintype "power_in"))
      (node (ref "D2") (pin "N13") (pinfunction "VCCAUX_N13") (pintype "power_in"))
      (node (ref "D2") (pin "N23") (pinfunction "VCCAUX_N23") (pintype "power_in"))
      (node (ref "D2") (pin "P12") (pinfunction "VCCAUX_P12") (pintype "power_in"))
      (node (ref "D2") (pin "P22") (pinfunction "VCCAUX_P22") (pintype "power_in"))
      (node (ref "D2") (pin "R13") (pinfunction "VCCAUX_R13") (pintype "power_in"))
      (node (ref "D2") (pin "R23") (pinfunction "VCCAUX_R23") (pintype "power_in"))
      (node (ref "D2") (pin "T12") (pinfunction "VCCAUX_T12") (pintype "power_in"))
      (node (ref "D2") (pin "T22") (pinfunction "VCCAUX_T22") (pintype "power_in"))
      (node (ref "D2") (pin "U13") (pinfunction "VCCAUX_U13") (pintype "power_in"))
      (node (ref "D2") (pin "U23") (pinfunction "VCCAUX_U23") (pintype "power_in"))
      (node (ref "D2") (pin "V12") (pinfunction "VCCAUX_V12") (pintype "power_in"))
      (node (ref "D2") (pin "V22") (pinfunction "VCCAUX_V22") (pintype "power_in"))
      (node (ref "D2") (pin "W13") (pinfunction "VCCAUX_W13") (pintype "power_in"))
      (node (ref "D2") (pin "W23") (pinfunction "VCCAUX_W23") (pintype "power_in"))
      (node (ref "D2") (pin "Y12") (pinfunction "VCCAUX_Y12") (pintype "power_in"))
      (node (ref "D2") (pin "Y22") (pinfunction "VCCAUX_Y22") (pintype "power_in"))
      (node (ref "R88") (pin "2") (pintype "passive"))
    )
    (net (code "5") (name "VCC3V3") (class "Default")
      (node (ref "C117") (pin "1") (pinfunction "1_1") (pintype "passive"))
      (node (ref "C124") (pin "1") (pinfunction "1_1") (pintype "passive"))
      (node (ref "C125") (pin "1") (pinfunction "1_1") (pintype "passive"))
      (node (ref "C126") (pin "1") (pinfunction "1_1") (pintype "passive"))
      (node (ref "C127") (pin "1") (pinfunction "1_1") (pintype "passive"))
      (node (ref "C128") (pin "1") (pinfunction "1_1") (pintype "passive"))
      (node (ref "C129") (pin "1") (pinfunction "1_1") (pintype "passive"))
      (node (ref "C130") (pin "1") (pinfunction "1_1") (pintype "passive"))
      (node (ref "C131") (pin "1") (pinfunction "1_1") (pintype "passive"))
      (node (ref "C132") (pin "1") (pinfunction "1_1") (pintype "passive"))
      (node (ref "C133") (pin "1") (pinfunction "1_1") (pintype "passive"))
      (node (ref "C134") (pin "1") (pinfunction "1_1") (pintype "passive"))
      (node (ref "C135") (pin "1") (pinfunction "1_1") (pintype "passive"))
      (node (ref "C136") (pin "1") (pinfunction "1_1") (pintype "passive"))
      (node (ref "C137") (pin "1") (pinfunction "1_1") (pintype "passive"))
      (node (ref "C138") (pin "1") (pinfunction "1_1") (pintype "passive"))
      (node (ref "C139") (pin "1") (pinfunction "1_1") (pintype "passive"))
      (node (ref "C140") (pin "1") (pinfunction "1_1") (pintype "passive"))
      (node (ref "C141") (pin "1") (pinfunction "1_1") (pintype "passive"))
      (node (ref "C142") (pin "1") (pinfunction "1_1") (pintype "passive"))
      (node (ref "C143") (pin "1") (pinfunction "1_1") (pintype "passive"))
      (node (ref "C144") (pin "1") (pinfunction "1_1") (pintype "passive"))
      (node (ref "C145") (pin "1") (pinfunction "1_1") (pintype "passive"))
      (node (ref "C146") (pin "1") (pinfunction "1_1") (pintype "passive"))
      (node (ref "C147") (pin "1") (pinfunction "1_1") (pintype "passive"))
      (node (ref "C148") (pin "1") (pinfunction "1_1") (pintype "passive"))
      (node (ref "C149") (pin "1") (pinfunction "1_1") (pintype "passive"))
      (node (ref "C150") (pin "1") (pinfunction "1_1") (pintype "passive"))
      (node (ref "C151") (pin "1") (pinfunction "1_1") (pintype "passive"))
      (node (ref "C152") (pin "1") (pinfunction "1_1") (pintype "passive"))
      (node (ref "C153") (pin "1") (pinfunction "1_1") (pintype "passive"))
      (node (ref "C154") (pin "1") (pinfunction "1_1") (pintype "passive"))
      (node (ref "C155") (pin "1") (pinfunction "1_1") (pintype "passive"))
      (node (ref "C156") (pin "1") (pinfunction "1_1") (pintype "passive"))
      (node (ref "C157") (pin "1") (pinfunction "1_1") (pintype "passive"))
      (node (ref "C158") (pin "1") (pinfunction "1_1") (pintype "passive"))
      (node (ref "C159") (pin "1") (pinfunction "1_1") (pintype "passive"))
      (node (ref "C160") (pin "1") (pinfunction "1_1") (pintype "passive"))
      (node (ref "C161") (pin "1") (pinfunction "1_1") (pintype "passive"))
      (node (ref "C162") (pin "1") (pinfunction "1_1") (pintype "passive"))
      (node (ref "C163") (pin "1") (pinfunction "1_1") (pintype "passive"))
      (node (ref "C164") (pin "1") (pinfunction "1_1") (pintype "passive"))
      (node (ref "C165") (pin "1") (pinfunction "1_1") (pintype "passive"))
      (node (ref "C166") (pin "1") (pinfunction "1_1") (pintype "passive"))
      (node (ref "C167") (pin "1") (pinfunction "1_1") (pintype "passive"))
      (node (ref "C168") (pin "1") (pinfunction "1_1") (pintype "passive"))
      (node (ref "C169") (pin "1") (pinfunction "1_1") (pintype "passive"))
      (node (ref "C170") (pin "1") (pinfunction "1_1") (pintype "passive"))
      (node (ref "C171") (pin "1") (pinfunction "1_1") (pintype "passive"))
      (node (ref "C172") (pin "1") (pinfunction "1_1") (pintype "passive"))
      (node (ref "C173") (pin "1") (pinfunction "1_1") (pintype "passive"))
      (node (ref "C179") (pin "1") (pinfunction "1_1") (pintype "passive"))
      (node (ref "C180") (pin "1") (pinfunction "1_1") (pintype "passive"))
      (node (ref "C181") (pin "1") (pinfunction "1_1") (pintype "passive"))
      (node (ref "C182") (pin "1") (pinfunction "1_1") (pintype "passive"))
      (node (ref "C183") (pin "1") (pinfunction "1_1") (pintype "passive"))
      (node (ref "C184") (pin "1") (pinfunction "1_1") (pintype "passive"))
      (node (ref "C185") (pin "1") (pinfunction "1_1") (pintype "passive"))
      (node (ref "C186") (pin "1") (pinfunction "1_1") (pintype "passive"))
      (node (ref "C187") (pin "1") (pinfunction "1_1") (pintype "passive"))
      (node (ref "C188") (pin "1") (pinfunction "1_1") (pintype "passive"))
      (node (ref "C210") (pin "1") (pinfunction "1_1") (pintype "passive"))
      (node (ref "C253") (pin "1") (pinfunction "1_1") (pintype "passive"))
      (node (ref "D2") (pin "A31") (pinfunction "VCCO_17_A31") (pintype "power_in"))
      (node (ref "D2") (pin "A6") (pinfunction "VCCO_37_A6") (pintype "power_in"))
      (node (ref "D2") (pin "AA31") (pinfunction "VCCO_14_AA31") (pintype "power_in"))
      (node (ref "D2") (pin "AA6") (pinfunction "VCCO_34_AA6") (pintype "power_in"))
      (node (ref "D2") (pin "AB28") (pinfunction "VCCO_14_AB28") (pintype "power_in"))
      (node (ref "D2") (pin "AB3") (pinfunction "VCCO_34_AB3") (pintype "power_in"))
      (node (ref "D2") (pin "AC10") (pinfunction "VCCO_34_AC10") (pintype "power_in"))
      (node (ref "D2") (pin "AC25") (pinfunction "VCCO_13_AC25") (pintype "power_in"))
      (node (ref "D2") (pin "AD32") (pinfunction "VCCO_13_AD32") (pintype "power_in"))
      (node (ref "D2") (pin "AD7") (pinfunction "VCCO_33_AD7") (pintype "power_in"))
      (node (ref "D2") (pin "AE29") (pinfunction "VCCO_13_AE29") (pintype "power_in"))
      (node (ref "D2") (pin "AE4") (pinfunction "VCCO_33_AE4") (pintype "power_in"))
      (node (ref "D2") (pin "AF1") (pinfunction "VCCO_33_AF1") (pintype "power_in"))
      (node (ref "D2") (pin "AF11") (pinfunction "VCCO_33_AF11") (pintype "power_in"))
      (node (ref "D2") (pin "AF26") (pinfunction "VCCO_13_AF26") (pintype "power_in"))
      (node (ref "D2") (pin "AG33") (pinfunction "VCCO_13_AG33") (pintype "power_in"))
      (node (ref "D2") (pin "AG8") (pinfunction "VCCO_33_AG8") (pintype "power_in"))
      (node (ref "D2") (pin "AH30") (pinfunction "VCCO_13_AH30") (pintype "power_in"))
      (node (ref "D2") (pin "AH5") (pinfunction "VCCO_33_AH5") (pintype "power_in"))
      (node (ref "D2") (pin "AJ2") (pinfunction "VCCO_32_AJ2") (pintype "power_in"))
      (node (ref "D2") (pin "AJ27") (pinfunction "VCCO_12_AJ27") (pintype "power_in"))
      (node (ref "D2") (pin "AK34") (pinfunction "VCCO_12_AK34") (pintype "power_in"))
      (node (ref "D2") (pin "AK9") (pinfunction "VCCO_32_AK9") (pintype "power_in"))
      (node (ref "D2") (pin "AL31") (pinfunction "VCCO_12_AL31") (pintype "power_in"))
      (node (ref "D2") (pin "AL6") (pinfunction "VCCO_32_AL6") (pintype "power_in"))
      (node (ref "D2") (pin "AM28") (pinfunction "VCCO_12_AM28") (pintype "power_in"))
      (node (ref "D2") (pin "AM3") (pinfunction "VCCO_32_AM3") (pintype "power_in"))
      (node (ref "D2") (pin "AN10") (pinfunction "VCCO_32_AN10") (pintype "power_in"))
      (node (ref "D2") (pin "AN25") (pinfunction "VCCO_12_AN25") (pintype "power_in"))
      (node (ref "D2") (pin "AP32") (pinfunction "VCCO_12_AP32") (pintype "power_in"))
      (node (ref "D2") (pin "AP7") (pinfunction "VCCO_32_AP7") (pintype "power_in"))
      (node (ref "D2") (pin "B28") (pinfunction "VCCO_17_B28") (pintype "power_in"))
      (node (ref "D2") (pin "B3") (pinfunction "VCCO_37_B3") (pintype "power_in"))
      (node (ref "D2") (pin "C10") (pinfunction "VCCO_37_C10") (pintype "power_in"))
      (node (ref "D2") (pin "C25") (pinfunction "VCCO_17_C25") (pintype "power_in"))
      (node (ref "D2") (pin "D32") (pinfunction "VCCO_17_D32") (pintype "power_in"))
      (node (ref "D2") (pin "D7") (pinfunction "VCCO_37_D7") (pintype "power_in"))
      (node (ref "D2") (pin "E29") (pinfunction "VCCO_17_E29") (pintype "power_in"))
      (node (ref "D2") (pin "E4") (pinfunction "VCCO_37_E4") (pintype "power_in"))
      (node (ref "D2") (pin "F1") (pinfunction "VCCO_36_F1") (pintype "power_in"))
      (node (ref "D2") (pin "F11") (pinfunction "VCCO_37_F11") (pintype "power_in"))
      (node (ref "D2") (pin "F26") (pinfunction "VCCO_17_F26") (pintype "power_in"))
      (node (ref "D2") (pin "G33") (pinfunction "VCCO_16_G33") (pintype "power_in"))
      (node (ref "D2") (pin "G8") (pinfunction "VCCO_36_G8") (pintype "power_in"))
      (node (ref "D2") (pin "H30") (pinfunction "VCCO_16_H30") (pintype "power_in"))
      (node (ref "D2") (pin "H5") (pinfunction "VCCO_36_H5") (pintype "power_in"))
      (node (ref "D2") (pin "J12") (pinfunction "VCCO_36_J12") (pintype "power_in"))
      (node (ref "D2") (pin "J2") (pinfunction "VCCO_36_J2") (pintype "power_in"))
      (node (ref "D2") (pin "J27") (pinfunction "VCCO_16_J27") (pintype "power_in"))
      (node (ref "D2") (pin "K24") (pinfunction "VCCO_16_K24") (pintype "power_in"))
      (node (ref "D2") (pin "K34") (pinfunction "VCCO_16_K34") (pintype "power_in"))
      (node (ref "D2") (pin "K9") (pinfunction "VCCO_36_K9") (pintype "power_in"))
      (node (ref "D2") (pin "L13") (pinfunction "VCCO_0_L13") (pintype "power_in"))
      (node (ref "D2") (pin "L31") (pinfunction "VCCO_16_L31") (pintype "power_in"))
      (node (ref "D2") (pin "L6") (pinfunction "VCCO_36_L6") (pintype "power_in"))
      (node (ref "D2") (pin "M28") (pinfunction "VCCO_15_M28") (pintype "power_in"))
      (node (ref "D2") (pin "M3") (pinfunction "VCCO_35_M3") (pintype "power_in"))
      (node (ref "D2") (pin "N10") (pinfunction "VCCO_35_N10") (pintype "power_in"))
      (node (ref "D2") (pin "N25") (pinfunction "VCCO_15_N25") (pintype "power_in"))
      (node (ref "D2") (pin "P32") (pinfunction "VCCO_15_P32") (pintype "power_in"))
      (node (ref "D2") (pin "P7") (pinfunction "VCCO_35_P7") (pintype "power_in"))
      (node (ref "D2") (pin "R29") (pinfunction "VCCO_15_R29") (pintype "power_in"))
      (node (ref "D2") (pin "R4") (pinfunction "VCCO_35_R4") (pintype "power_in"))
      (node (ref "D2") (pin "T1") (pinfunction "VCCO_35_T1") (pintype "power_in"))
      (node (ref "D2") (pin "T11") (pinfunction "VCCO_0_T11") (pintype "power_in"))
      (node (ref "D2") (pin "T18") (pinfunction "VCCADC_0_T18") (pintype "power_in"))
      (node (ref "D2") (pin "T26") (pinfunction "VCCO_15_T26") (pintype "power_in"))
      (node (ref "D2") (pin "U33") (pinfunction "VCCO_15_U33") (pintype "power_in"))
      (node (ref "D2") (pin "U8") (pinfunction "VCCO_35_U8") (pintype "power_in"))
      (node (ref "D2") (pin "V30") (pinfunction "VCCO_14_V30") (pintype "power_in"))
      (node (ref "D2") (pin "V5") (pinfunction "VCCO_34_V5") (pintype "power_in"))
      (node (ref "D2") (pin "W2") (pinfunction "VCCO_34_W2") (pintype "power_in"))
      (node (ref "D2") (pin "W27") (pinfunction "VCCO_14_W27") (pintype "power_in"))
      (node (ref "D2") (pin "Y24") (pinfunction "VCCO_14_Y24") (pintype "power_in"))
      (node (ref "D2") (pin "Y34") (pinfunction "VCCO_14_Y34") (pintype "power_in"))
      (node (ref "D2") (pin "Y9") (pinfunction "VCCO_34_Y9") (pintype "power_in"))
    )
  )
)
